# 2_Nets.net
KiCad netlist of a schematic drawn in Altium Designer
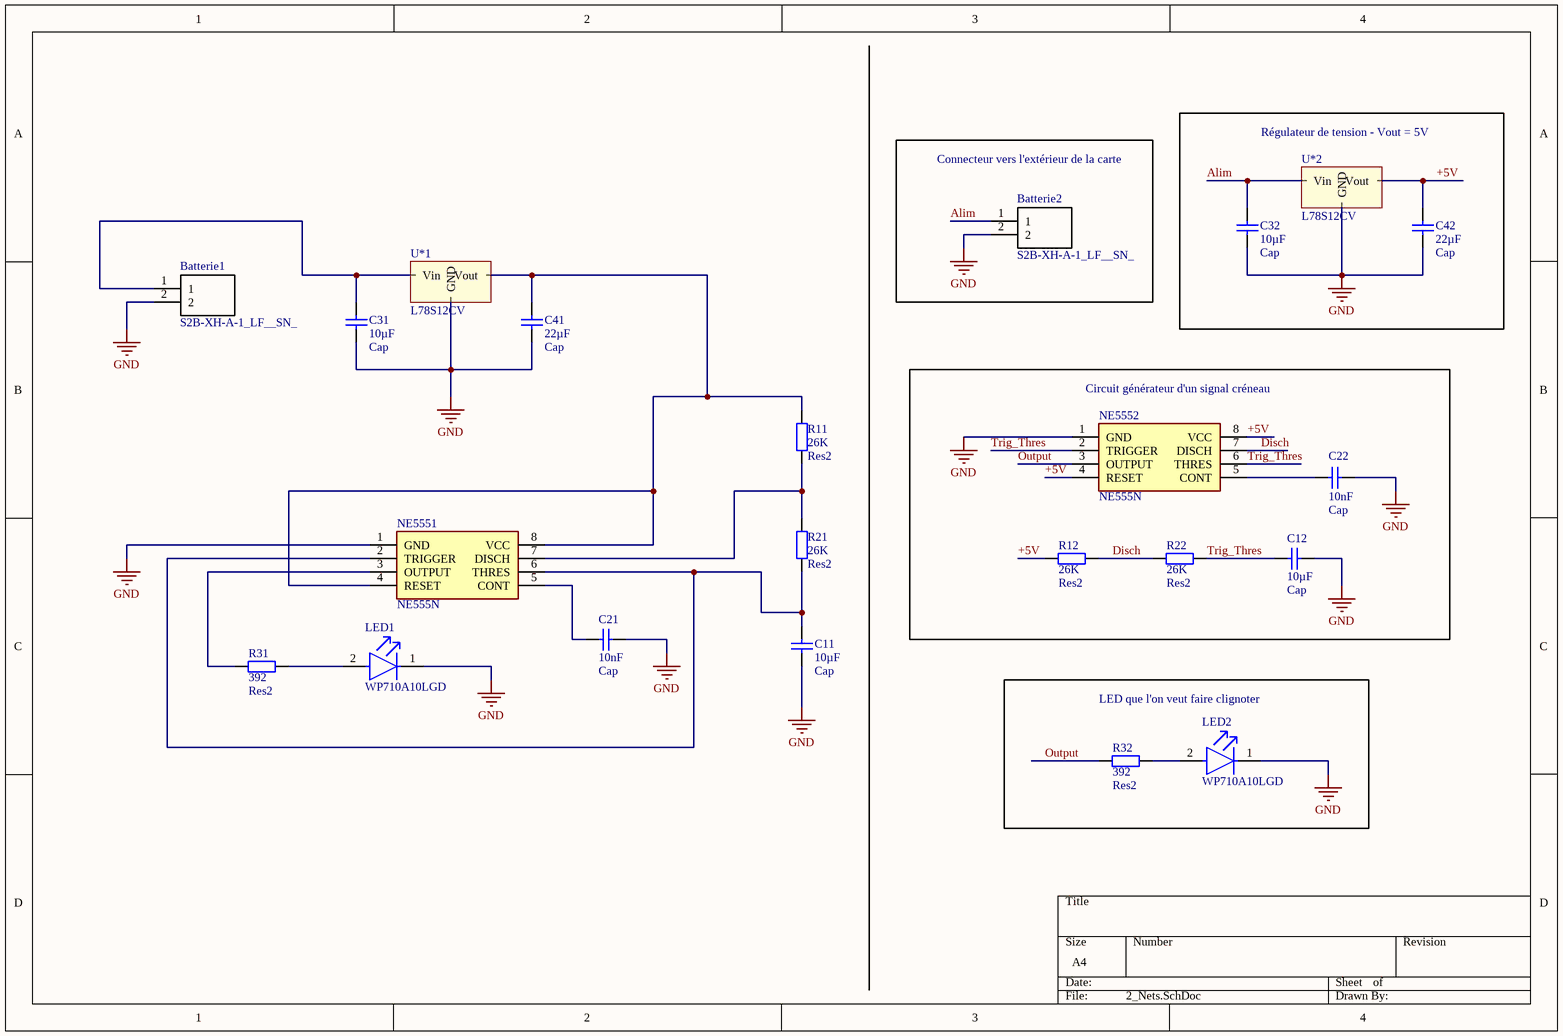
[diagram p0: 2_Nets.SchDoc]

(export (version "E")
  (design (tool "Eeschema 10.0.6"))
  (components
    (comp (ref "Batterie1")
      (value "S2B-XH-A-1_LF__SN_")
      (footprint "S2B-XH-A")
      (description "Connector")
      (fields (field (name "MANUFACTURER_PART_NUMBER") "S2B-XH-A-1(LF)(SN)"))
      (libsource (lib "SamacSys") (part "S2B-XH-A-1_LF__SN_"))
    )
    (comp (ref "Batterie2")
      (value "S2B-XH-A-1_LF__SN_")
      (footprint "S2B-XH-A")
      (description "Connector")
      (fields (field (name "MANUFACTURER_PART_NUMBER") "S2B-XH-A-1(LF)(SN)"))
      (libsource (lib "SamacSys") (part "S2B-XH-A-1_LF__SN_"))
    )
    (comp (ref "C11")
      (value "Cap")
      (footprint "Capacitor 1206")
      (description "Capacitor")
      (fields (field (name "ALTIUM_VALUE") "10µF") (field (name "PUBLISHER") "Altium Limited"))
      (libsource (lib "Miscellaneous Devices") (part "Cap"))
    )
    (comp (ref "C12")
      (value "Cap")
      (footprint "Capacitor 1206")
      (description "Capacitor")
      (fields (field (name "ALTIUM_VALUE") "10µF") (field (name "PUBLISHER") "Altium Limited"))
      (libsource (lib "Miscellaneous Devices") (part "Cap"))
    )
    (comp (ref "C21")
      (value "Cap")
      (footprint "Capacitor 1206")
      (description "Capacitor")
      (fields (field (name "ALTIUM_VALUE") "10nF") (field (name "PUBLISHER") "Altium Limited"))
      (libsource (lib "Miscellaneous Devices") (part "Cap"))
    )
    (comp (ref "C22")
      (value "Cap")
      (footprint "Capacitor 1206")
      (description "Capacitor")
      (fields (field (name "ALTIUM_VALUE") "10nF") (field (name "PUBLISHER") "Altium Limited"))
      (libsource (lib "Miscellaneous Devices") (part "Cap"))
    )
    (comp (ref "C31")
      (value "Cap")
      (footprint "Capacitor 1206")
      (description "Capacitor")
      (fields (field (name "ALTIUM_VALUE") "10µF") (field (name "PUBLISHER") "Altium Limited"))
      (libsource (lib "Miscellaneous Devices") (part "Cap"))
    )
    (comp (ref "C32")
      (value "Cap")
      (footprint "Capacitor 1206")
      (description "Capacitor")
      (fields (field (name "ALTIUM_VALUE") "10µF") (field (name "PUBLISHER") "Altium Limited"))
      (libsource (lib "Miscellaneous Devices") (part "Cap"))
    )
    (comp (ref "C41")
      (value "Cap")
      (footprint "Capacitor 1206")
      (description "Capacitor")
      (fields (field (name "ALTIUM_VALUE") "22µF") (field (name "PUBLISHER") "Altium Limited"))
      (libsource (lib "Miscellaneous Devices") (part "Cap"))
    )
    (comp (ref "C42")
      (value "Cap")
      (footprint "Capacitor 1206")
      (description "Capacitor")
      (fields (field (name "ALTIUM_VALUE") "22µF") (field (name "PUBLISHER") "Altium Limited"))
      (libsource (lib "Miscellaneous Devices") (part "Cap"))
    )
    (comp (ref "LED1")
      (value "WP710A10LGD")
      (footprint "FP-WP710A10LGD-MFG")
      (description "WP710A10LGD LED Thru-Hole PCB Green T-1 3mm Green Lens 2 mA 568 nm 2 mcd Round")
      (libsource (lib "Altium Content Vault") (part "8706943c75ba83719d021d2fdc84c58"))
    )
    (comp (ref "LED2")
      (value "WP710A10LGD")
      (footprint "FP-WP710A10LGD-MFG")
      (description "WP710A10LGD LED Thru-Hole PCB Green T-1 3mm Green Lens 2 mA 568 nm 2 mcd Round")
      (libsource (lib "Altium Content Vault") (part "8706943c75ba83719d021d2fdc84c58"))
    )
    (comp (ref "NE5551")
      (value "NE555N")
      (footprint "SamacSys:DIP762W56P254L959H533Q8N")
      (description "Integrated Circuit")
      (libsource (lib "Robot_2020") (part "NE555N"))
    )
    (comp (ref "NE5552")
      (value "NE555N")
      (footprint "SamacSys:DIP762W56P254L959H533Q8N")
      (description "Integrated Circuit")
      (libsource (lib "Robot_2020") (part "NE555N"))
    )
    (comp (ref "R11")
      (value "Res2")
      (footprint "Resistor 1206")
      (description "Resistor")
      (fields (field (name "ALTIUM_VALUE") "26K") (field (name "PUBLISHER") "Altium Limited"))
      (libsource (lib "") (part "Res2_1"))
    )
    (comp (ref "R12")
      (value "Res2")
      (footprint "Resistor 1206")
      (description "Resistor")
      (fields (field (name "ALTIUM_VALUE") "26K") (field (name "PUBLISHER") "Altium Limited"))
      (libsource (lib "Miscellaneous Devices") (part "Res2"))
    )
    (comp (ref "R21")
      (value "Res2")
      (footprint "Resistor 1206")
      (description "Resistor")
      (fields (field (name "ALTIUM_VALUE") "26K") (field (name "PUBLISHER") "Altium Limited"))
      (libsource (lib "") (part "Res2_1"))
    )
    (comp (ref "R22")
      (value "Res2")
      (footprint "Resistor 1206")
      (description "Resistor")
      (fields (field (name "ALTIUM_VALUE") "26K") (field (name "PUBLISHER") "Altium Limited"))
      (libsource (lib "Miscellaneous Devices") (part "Res2"))
    )
    (comp (ref "R31")
      (value "Res2")
      (footprint "Resistor 1206")
      (description "Resistor")
      (fields (field (name "ALTIUM_VALUE") "392") (field (name "PUBLISHER") "Altium Limited"))
      (libsource (lib "Miscellaneous Devices") (part "Res2"))
    )
    (comp (ref "R32")
      (value "Res2")
      (footprint "Resistor 1206")
      (description "Resistor")
      (fields (field (name "ALTIUM_VALUE") "392") (field (name "PUBLISHER") "Altium Limited"))
      (libsource (lib "Miscellaneous Devices") (part "Res2"))
    )
    (comp (ref "U*1")
      (value "L78S12CV")
      (footprint "R-78B")
      (libsource (lib "Robot_2020") (part "Régulateur de tension linéaire"))
    )
    (comp (ref "U*2")
      (value "L78S12CV")
      (footprint "R-78B")
      (libsource (lib "Robot_2020") (part "Régulateur de tension linéaire"))
    )
  )
  (nets
    (net (code "1") (name "/+5V") (class "Default")
      (node (ref "C42") (pin "2") (pinfunction "2_2") (pintype "passive"))
      (node (ref "NE5552") (pin "4") (pinfunction "RESET_4") (pintype "passive"))
      (node (ref "NE5552") (pin "8") (pinfunction "VCC_8") (pintype "passive"))
      (node (ref "R12") (pin "2") (pinfunction "2_2") (pintype "passive"))
      (node (ref "U*2") (pin "1") (pinfunction "Vout_1") (pintype "passive"))
    )
    (net (code "2") (name "/Alim") (class "Default")
      (node (ref "Batterie2") (pin "1") (pinfunction "1_1") (pintype "passive"))
      (node (ref "C32") (pin "1") (pinfunction "1_1") (pintype "passive"))
      (node (ref "U*2") (pin "3") (pinfunction "Vin_3") (pintype "passive"))
    )
    (net (code "3") (name "/Disch") (class "Default")
      (node (ref "NE5552") (pin "7") (pinfunction "DISCH_7") (pintype "passive"))
      (node (ref "R12") (pin "1") (pinfunction "1_1") (pintype "passive"))
      (node (ref "R22") (pin "2") (pinfunction "2_2") (pintype "passive"))
    )
    (net (code "4") (name "/Output") (class "Default")
      (node (ref "NE5552") (pin "3") (pinfunction "OUTPUT_3") (pintype "passive"))
      (node (ref "R32") (pin "2") (pinfunction "2_2") (pintype "passive"))
    )
    (net (code "5") (name "/Trig_Thres") (class "Default")
      (node (ref "C12") (pin "2") (pinfunction "2_2") (pintype "passive"))
      (node (ref "NE5552") (pin "2") (pinfunction "TRIGGER_2") (pintype "passive"))
      (node (ref "NE5552") (pin "6") (pinfunction "THRES_6") (pintype "passive"))
      (node (ref "R22") (pin "1") (pinfunction "1_1") (pintype "passive"))
    )
    (net (code "6") (name "GND") (class "Default")
      (node (ref "Batterie1") (pin "2") (pinfunction "2_2") (pintype "passive"))
      (node (ref "Batterie2") (pin "2") (pinfunction "2_2") (pintype "passive"))
      (node (ref "C11") (pin "1") (pinfunction "1_1") (pintype "passive"))
      (node (ref "C12") (pin "1") (pinfunction "1_1") (pintype "passive"))
      (node (ref "C21") (pin "2") (pinfunction "2_2") (pintype "passive"))
      (node (ref "C22") (pin "2") (pinfunction "2_2") (pintype "passive"))
      (node (ref "C31") (pin "2") (pinfunction "2_2") (pintype "passive"))
      (node (ref "C32") (pin "2") (pinfunction "2_2") (pintype "passive"))
      (node (ref "C41") (pin "1") (pinfunction "1_1") (pintype "passive"))
      (node (ref "C42") (pin "1") (pinfunction "1_1") (pintype "passive"))
      (node (ref "LED1") (pin "1") (pinfunction "C_1") (pintype "passive"))
      (node (ref "LED2") (pin "1") (pinfunction "C_1") (pintype "passive"))
      (node (ref "NE5551") (pin "1") (pinfunction "GND_1") (pintype "passive"))
      (node (ref "NE5552") (pin "1") (pinfunction "GND_1") (pintype "passive"))
      (node (ref "U*1") (pin "2") (pinfunction "GND_2") (pintype "passive"))
      (node (ref "U*2") (pin "2") (pinfunction "GND_2") (pintype "passive"))
    )
    (net (code "7") (name "Net-(LED1-A)") (class "Default")
      (node (ref "LED1") (pin "2") (pinfunction "A_2") (pintype "passive"))
      (node (ref "R31") (pin "1") (pinfunction "1_1") (pintype "passive"))
    )
    (net (code "8") (name "Net-(LED2-A)") (class "Default")
      (node (ref "LED2") (pin "2") (pinfunction "A_2") (pintype "passive"))
      (node (ref "R32") (pin "1") (pinfunction "1_1") (pintype "passive"))
    )
    (net (code "9") (name "Net-(NE5551-CONT)") (class "Default")
      (node (ref "C21") (pin "1") (pinfunction "1_1") (pintype "passive"))
      (node (ref "NE5551") (pin "5") (pinfunction "CONT_5") (pintype "passive"))
    )
    (net (code "10") (name "Net-(NE5551-DISCH)") (class "Default")
      (node (ref "NE5551") (pin "7") (pinfunction "DISCH_7") (pintype "passive"))
      (node (ref "R11") (pin "1") (pinfunction "1_1") (pintype "passive"))
      (node (ref "R21") (pin "2") (pinfunction "2_2") (pintype "passive"))
    )
    (net (code "11") (name "Net-(NE5551-OUTPUT)") (class "Default")
      (node (ref "NE5551") (pin "3") (pinfunction "OUTPUT_3") (pintype "passive"))
      (node (ref "R31") (pin "2") (pinfunction "2_2") (pintype "passive"))
    )
    (net (code "12") (name "Net-(NE5551-RESET)") (class "Default")
      (node (ref "C41") (pin "2") (pinfunction "2_2") (pintype "passive"))
      (node (ref "NE5551") (pin "4") (pinfunction "RESET_4") (pintype "passive"))
      (node (ref "NE5551") (pin "8") (pinfunction "VCC_8") (pintype "passive"))
      (node (ref "R11") (pin "2") (pinfunction "2_2") (pintype "passive"))
      (node (ref "U*1") (pin "1") (pinfunction "Vout_1") (pintype "passive"))
    )
    (net (code "13") (name "Net-(NE5551-THRES)") (class "Default")
      (node (ref "C11") (pin "2") (pinfunction "2_2") (pintype "passive"))
      (node (ref "NE5551") (pin "2") (pinfunction "TRIGGER_2") (pintype "passive"))
      (node (ref "NE5551") (pin "6") (pinfunction "THRES_6") (pintype "passive"))
      (node (ref "R21") (pin "1") (pinfunction "1_1") (pintype "passive"))
    )
    (net (code "14") (name "Net-(NE5552-CONT)") (class "Default")
      (node (ref "C22") (pin "1") (pinfunction "1_1") (pintype "passive"))
      (node (ref "NE5552") (pin "5") (pinfunction "CONT_5") (pintype "passive"))
    )
    (net (code "15") (name "Net-(U*1-Vin)") (class "Default")
      (node (ref "Batterie1") (pin "1") (pinfunction "1_1") (pintype "passive"))
      (node (ref "C31") (pin "1") (pinfunction "1_1") (pintype "passive"))
      (node (ref "U*1") (pin "3") (pinfunction "Vin_3") (pintype "passive"))
    )
  )
)
